# RevA.net
KiCad netlist of a schematic drawn in EAGLE
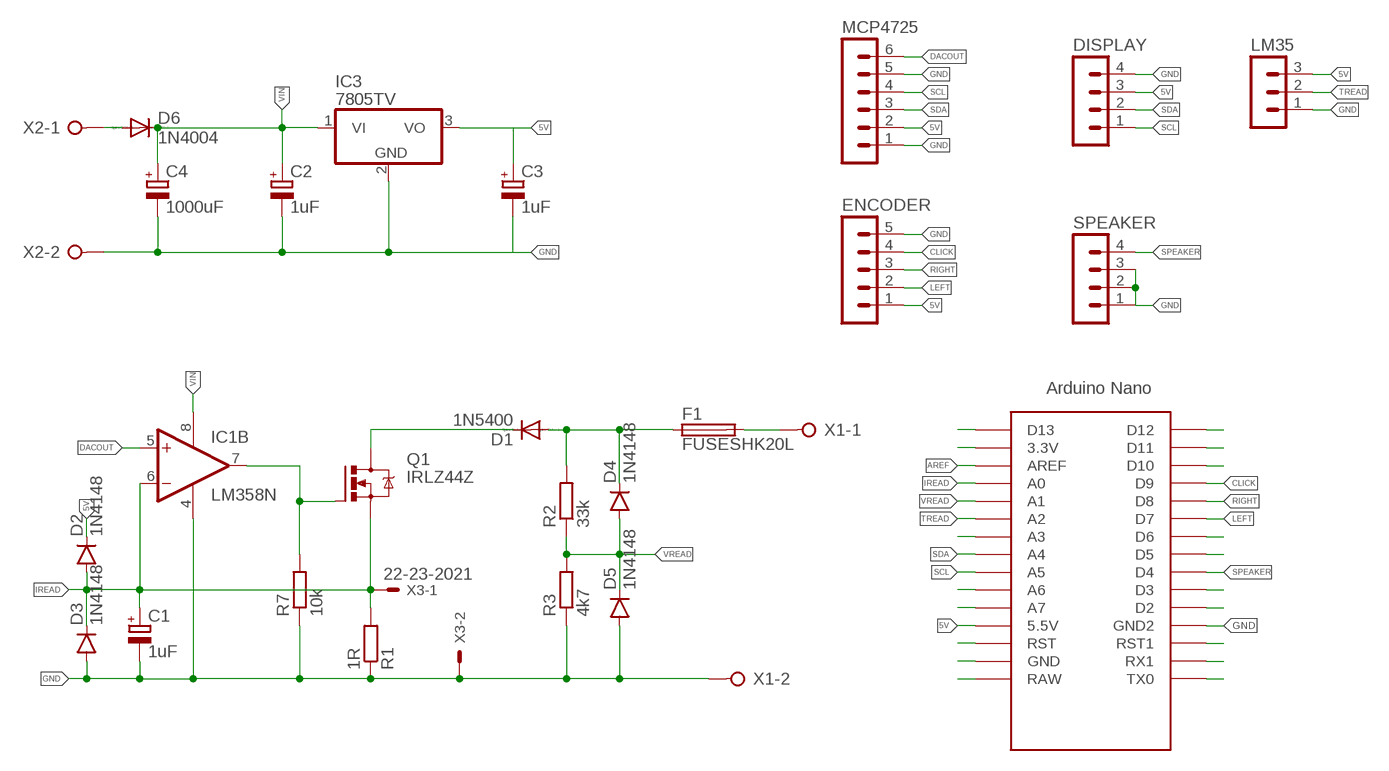
[diagram p0: schematic, sheet 1]

(export (version "E")
  (design (tool "Eeschema 10.0.6"))
  (components
    (comp (ref "C1")
      (value "1uF")
      (footprint "eagle-import:E2-5")
      (libsource (lib "eagle-import") (part "CPOL-EUE2-5"))
    )
    (comp (ref "C2")
      (value "1uF")
      (footprint "eagle-import:E5-5")
      (libsource (lib "eagle-import") (part "CPOL-EUE5-5"))
    )
    (comp (ref "C3")
      (value "1uF")
      (footprint "eagle-import:E5-5")
      (libsource (lib "eagle-import") (part "CPOL-EUE5-5"))
    )
    (comp (ref "C4")
      (value "1000uF")
      (footprint "eagle-import:E5-10,5")
      (libsource (lib "eagle-import") (part "CPOL-EUE5-10.5"))
    )
    (comp (ref "D1")
      (value "1N5400")
      (footprint "eagle-import:DO201-15")
      (libsource (lib "eagle-import") (part "1N5400"))
    )
    (comp (ref "D2")
      (value "1N4148")
      (footprint "eagle-import:DIODE-1N4148")
      (libsource (lib "eagle-import") (part "DIODE1N4148"))
    )
    (comp (ref "D3")
      (value "1N4148")
      (footprint "eagle-import:DIODE-1N4148")
      (libsource (lib "eagle-import") (part "DIODE1N4148"))
    )
    (comp (ref "D4")
      (value "1N4148")
      (footprint "eagle-import:DIODE-1N4148")
      (libsource (lib "eagle-import") (part "DIODE1N4148"))
    )
    (comp (ref "D5")
      (value "1N4148")
      (footprint "eagle-import:DIODE-1N4148")
      (libsource (lib "eagle-import") (part "DIODE1N4148"))
    )
    (comp (ref "D6")
      (value "1N4004")
      (footprint "eagle-import:DO41-10")
      (libsource (lib "eagle-import") (part "1N4004"))
    )
    (comp (ref "DISPLAY")
      (value "MA04-1")
      (footprint "eagle-import:MA04-1")
      (libsource (lib "eagle-import") (part "MA04-1"))
    )
    (comp (ref "ENCODER")
      (value "MA05-1")
      (footprint "eagle-import:MA05-1")
      (libsource (lib "eagle-import") (part "MA05-1"))
    )
    (comp (ref "F1")
      (value "FUSESHK20L")
      (footprint "eagle-import:SHK20L")
      (libsource (lib "eagle-import") (part "FUSESHK20L"))
    )
    (comp (ref "IC1")
      (value "LM358N")
      (footprint "eagle-import:DIL08")
      (libsource (lib "eagle-import") (part "LM358N"))
    )
    (comp (ref "IC3")
      (value "7805TV")
      (footprint "eagle-import:TO220V")
      (libsource (lib "eagle-import") (part "78TV05"))
    )
    (comp (ref "LM35")
      (value "MA03-1")
      (footprint "eagle-import:MA03-1")
      (libsource (lib "eagle-import") (part "MA03-1"))
    )
    (comp (ref "MCP4725")
      (value "MA06-1")
      (footprint "eagle-import:MA06-1")
      (libsource (lib "eagle-import") (part "MA06-1"))
    )
    (comp (ref "Q1")
      (value "IRLZ44Z")
      (footprint "eagle-import:TO220BH")
      (libsource (lib "eagle-import") (part "IRLZ44Z"))
    )
    (comp (ref "R1")
      (value "1R")
      (footprint "eagle-import:0309_12")
      (libsource (lib "eagle-import") (part "R-EU_0309/12"))
    )
    (comp (ref "R2")
      (value "33k")
      (footprint "eagle-import:0207_10")
      (libsource (lib "eagle-import") (part "R-EU_0207/10"))
    )
    (comp (ref "R3")
      (value "4k7")
      (footprint "eagle-import:0207_10")
      (libsource (lib "eagle-import") (part "R-EU_0207/10"))
    )
    (comp (ref "R7")
      (value "10k")
      (footprint "eagle-import:0207_10")
      (libsource (lib "eagle-import") (part "R-EU_0207/10"))
    )
    (comp (ref "SPEAKER")
      (value "MA04-1")
      (footprint "eagle-import:MA04-1")
      (libsource (lib "eagle-import") (part "MA04-1"))
    )
    (comp (ref "U$1")
      (value "NANO")
      (footprint "eagle-import:NANO")
      (libsource (lib "eagle-import") (part "NANO"))
    )
    (comp (ref "X1")
      (value "W237-02P")
      (footprint "eagle-import:W237-132")
      (libsource (lib "eagle-import") (part "W237-02P"))
    )
    (comp (ref "X2")
      (value "W237-02P")
      (footprint "eagle-import:W237-132")
      (libsource (lib "eagle-import") (part "W237-02P"))
    )
    (comp (ref "X3")
      (value "22-23-2021")
      (footprint "eagle-import:22-23-2021")
      (fields (field (name "MF") "MOLEX"))
      (libsource (lib "eagle-import") (part "22-23-2021"))
    )
  )
  (nets
    (net (code "1") (name "5V") (class "Default")
      (node (ref "C3") (pin "+") (pinfunction "+_+") (pintype "passive"))
      (node (ref "D2") (pin "C") (pinfunction "C_C") (pintype "passive"))
      (node (ref "DISPLAY") (pin "3") (pinfunction "3_3") (pintype "passive"))
      (node (ref "ENCODER") (pin "1") (pinfunction "1_1") (pintype "passive"))
      (node (ref "IC3") (pin "3") (pinfunction "VO_3") (pintype "passive"))
      (node (ref "LM35") (pin "3") (pinfunction "3_3") (pintype "passive"))
      (node (ref "MCP4725") (pin "2") (pinfunction "2_2") (pintype "passive"))
      (node (ref "U$1") (pin "5V") (pinfunction "5.5V_5V") (pintype "bidirectional"))
    )
    (net (code "2") (name "AREF") (class "Default")
      (node (ref "U$1") (pin "AREF") (pinfunction "AREF_AREF") (pintype "bidirectional"))
    )
    (net (code "3") (name "CLICK") (class "Default")
      (node (ref "ENCODER") (pin "4") (pinfunction "4_4") (pintype "passive"))
      (node (ref "U$1") (pin "D9") (pinfunction "D9_D9") (pintype "bidirectional"))
    )
    (net (code "4") (name "DACOUT") (class "Default")
      (node (ref "IC1") (pin "5") (pinfunction "+IN_5") (pintype "input"))
      (node (ref "MCP4725") (pin "6") (pinfunction "6_6") (pintype "passive"))
    )
    (net (code "5") (name "GND") (class "Default")
      (node (ref "C1") (pin "-") (pinfunction "-_-") (pintype "passive"))
      (node (ref "C2") (pin "-") (pinfunction "-_-") (pintype "passive"))
      (node (ref "C3") (pin "-") (pinfunction "-_-") (pintype "passive"))
      (node (ref "C4") (pin "-") (pinfunction "-_-") (pintype "passive"))
      (node (ref "D3") (pin "A") (pinfunction "A_A") (pintype "passive"))
      (node (ref "D5") (pin "A") (pinfunction "A_A") (pintype "passive"))
      (node (ref "DISPLAY") (pin "4") (pinfunction "4_4") (pintype "passive"))
      (node (ref "ENCODER") (pin "5") (pinfunction "5_5") (pintype "passive"))
      (node (ref "IC1") (pin "4") (pinfunction "V-_4") (pintype "power_in"))
      (node (ref "IC3") (pin "2") (pinfunction "GND_2") (pintype "passive"))
      (node (ref "LM35") (pin "1") (pinfunction "1_1") (pintype "passive"))
      (node (ref "MCP4725") (pin "1") (pinfunction "1_1") (pintype "passive"))
      (node (ref "MCP4725") (pin "5") (pinfunction "5_5") (pintype "passive"))
      (node (ref "R1") (pin "1") (pinfunction "1_1") (pintype "passive"))
      (node (ref "R3") (pin "1") (pinfunction "1_1") (pintype "passive"))
      (node (ref "R7") (pin "1") (pinfunction "1_1") (pintype "passive"))
      (node (ref "SPEAKER") (pin "1") (pinfunction "1_1") (pintype "passive"))
      (node (ref "SPEAKER") (pin "2") (pinfunction "2_2") (pintype "passive"))
      (node (ref "SPEAKER") (pin "3") (pinfunction "3_3") (pintype "passive"))
      (node (ref "U$1") (pin "GND1") (pinfunction "GND2_GND1") (pintype "bidirectional"))
      (node (ref "X1") (pin "2") (pinfunction "KL_2") (pintype "passive"))
      (node (ref "X2") (pin "2") (pinfunction "KL_2") (pintype "passive"))
      (node (ref "X3") (pin "2") (pinfunction "S_2") (pintype "passive"))
    )
    (net (code "6") (name "IREAD") (class "Default")
      (node (ref "C1") (pin "+") (pinfunction "+_+") (pintype "passive"))
      (node (ref "D2") (pin "A") (pinfunction "A_A") (pintype "passive"))
      (node (ref "D3") (pin "C") (pinfunction "C_C") (pintype "passive"))
      (node (ref "IC1") (pin "6") (pinfunction "-IN_6") (pintype "input"))
      (node (ref "Q1") (pin "S") (pinfunction "S_S") (pintype "passive"))
      (node (ref "R1") (pin "2") (pinfunction "2_2") (pintype "passive"))
      (node (ref "U$1") (pin "A0") (pinfunction "A0_A0") (pintype "bidirectional"))
      (node (ref "X3") (pin "1") (pinfunction "S_1") (pintype "passive"))
    )
    (net (code "7") (name "LEFT") (class "Default")
      (node (ref "ENCODER") (pin "2") (pinfunction "2_2") (pintype "passive"))
      (node (ref "U$1") (pin "D7") (pinfunction "D7_D7") (pintype "bidirectional"))
    )
    (net (code "8") (name "Net-(D1-PadC)") (class "Default")
      (node (ref "D1") (pin "C") (pinfunction "C_C") (pintype "passive"))
      (node (ref "Q1") (pin "D") (pinfunction "D_D") (pintype "passive"))
    )
    (net (code "9") (name "Net-(F1-1)") (class "Default")
      (node (ref "D1") (pin "A") (pinfunction "A_A") (pintype "passive"))
      (node (ref "D4") (pin "C") (pinfunction "C_C") (pintype "passive"))
      (node (ref "F1") (pin "1A") (pinfunction "1_1A") (pintype "passive"))
      (node (ref "R2") (pin "2") (pinfunction "2_2") (pintype "passive"))
    )
    (net (code "10") (name "Net-(F1-2)") (class "Default")
      (node (ref "F1") (pin "2A") (pinfunction "2_2A") (pintype "passive"))
      (node (ref "X1") (pin "1") (pinfunction "KL_1") (pintype "passive"))
    )
    (net (code "11") (name "Net-(IC1B-OUT)") (class "Default")
      (node (ref "IC1") (pin "7") (pinfunction "OUT_7") (pintype "output"))
      (node (ref "Q1") (pin "G") (pinfunction "G_G") (pintype "passive"))
      (node (ref "R7") (pin "2") (pinfunction "2_2") (pintype "passive"))
    )
    (net (code "12") (name "Net-(X2A-KL)") (class "Default")
      (node (ref "D6") (pin "A") (pinfunction "A_A") (pintype "passive"))
      (node (ref "X2") (pin "1") (pinfunction "KL_1") (pintype "passive"))
    )
    (net (code "13") (name "RIGHT") (class "Default")
      (node (ref "ENCODER") (pin "3") (pinfunction "3_3") (pintype "passive"))
      (node (ref "U$1") (pin "D8") (pinfunction "D8_D8") (pintype "bidirectional"))
    )
    (net (code "14") (name "SCL") (class "Default")
      (node (ref "DISPLAY") (pin "1") (pinfunction "1_1") (pintype "passive"))
      (node (ref "MCP4725") (pin "4") (pinfunction "4_4") (pintype "passive"))
      (node (ref "U$1") (pin "A5") (pinfunction "A5_A5") (pintype "bidirectional"))
    )
    (net (code "15") (name "SDA") (class "Default")
      (node (ref "DISPLAY") (pin "2") (pinfunction "2_2") (pintype "passive"))
      (node (ref "MCP4725") (pin "3") (pinfunction "3_3") (pintype "passive"))
      (node (ref "U$1") (pin "A4") (pinfunction "A4_A4") (pintype "bidirectional"))
    )
    (net (code "16") (name "SPEAKER") (class "Default")
      (node (ref "SPEAKER") (pin "4") (pinfunction "4_4") (pintype "passive"))
      (node (ref "U$1") (pin "D4") (pinfunction "D4_D4") (pintype "bidirectional"))
    )
    (net (code "17") (name "TREAD") (class "Default")
      (node (ref "LM35") (pin "2") (pinfunction "2_2") (pintype "passive"))
      (node (ref "U$1") (pin "A2") (pinfunction "A2_A2") (pintype "bidirectional"))
    )
    (net (code "18") (name "VIN") (class "Default")
      (node (ref "C2") (pin "+") (pinfunction "+_+") (pintype "passive"))
      (node (ref "C4") (pin "+") (pinfunction "+_+") (pintype "passive"))
      (node (ref "D6") (pin "C") (pinfunction "C_C") (pintype "passive"))
      (node (ref "IC1") (pin "8") (pinfunction "V+_8") (pintype "power_in"))
      (node (ref "IC3") (pin "1") (pinfunction "VI_1") (pintype "input"))
    )
    (net (code "19") (name "VREAD") (class "Default")
      (node (ref "D4") (pin "A") (pinfunction "A_A") (pintype "passive"))
      (node (ref "D5") (pin "C") (pinfunction "C_C") (pintype "passive"))
      (node (ref "R2") (pin "1") (pinfunction "1_1") (pintype "passive"))
      (node (ref "R3") (pin "2") (pinfunction "2_2") (pintype "passive"))
      (node (ref "U$1") (pin "A1") (pinfunction "A1_A1") (pintype "bidirectional"))
    )
    (net (code "20") (name "unconnected-(U$1-Pad3.3V)") (class "Default")
      (node (ref "U$1") (pin "3.3V") (pinfunction "3.3V_3.3V") (pintype "bidirectional"))
    )
    (net (code "21") (name "unconnected-(U$1-PadA3)") (class "Default")
      (node (ref "U$1") (pin "A3") (pinfunction "A3_A3") (pintype "bidirectional"))
    )
    (net (code "22") (name "unconnected-(U$1-PadA6)") (class "Default")
      (node (ref "U$1") (pin "A6") (pinfunction "A6_A6") (pintype "bidirectional"))
    )
    (net (code "23") (name "unconnected-(U$1-PadA7)") (class "Default")
      (node (ref "U$1") (pin "A7") (pinfunction "A7_A7") (pintype "bidirectional"))
    )
    (net (code "24") (name "unconnected-(U$1-PadD2)") (class "Default")
      (node (ref "U$1") (pin "D2") (pinfunction "D2_D2") (pintype "bidirectional"))
    )
    (net (code "25") (name "unconnected-(U$1-PadD3)") (class "Default")
      (node (ref "U$1") (pin "D3") (pinfunction "D3_D3") (pintype "bidirectional"))
    )
    (net (code "26") (name "unconnected-(U$1-PadD5)") (class "Default")
      (node (ref "U$1") (pin "D5") (pinfunction "D5_D5") (pintype "bidirectional"))
    )
    (net (code "27") (name "unconnected-(U$1-PadD6)") (class "Default")
      (node (ref "U$1") (pin "D6") (pinfunction "D6_D6") (pintype "bidirectional"))
    )
    (net (code "28") (name "unconnected-(U$1-PadD10)") (class "Default")
      (node (ref "U$1") (pin "D10") (pinfunction "D10_D10") (pintype "bidirectional"))
    )
    (net (code "29") (name "unconnected-(U$1-PadD11)") (class "Default")
      (node (ref "U$1") (pin "D11") (pinfunction "D11_D11") (pintype "bidirectional"))
    )
    (net (code "30") (name "unconnected-(U$1-PadD12)") (class "Default")
      (node (ref "U$1") (pin "D12") (pinfunction "D12_D12") (pintype "bidirectional"))
    )
    (net (code "31") (name "unconnected-(U$1-PadD13)") (class "Default")
      (node (ref "U$1") (pin "D13") (pinfunction "D13_D13") (pintype "bidirectional"))
    )
    (net (code "32") (name "unconnected-(U$1-PadGND)") (class "Default")
      (node (ref "U$1") (pin "GND") (pinfunction "GND_GND") (pintype "bidirectional"))
    )
    (net (code "33") (name "unconnected-(U$1-PadICSP1)") (class "Default")
      (node (ref "U$1") (pin "ICSP1") (pinfunction "ICSP1_ICSP1") (pintype "bidirectional"))
    )
    (net (code "34") (name "unconnected-(U$1-PadICSP2)") (class "Default")
      (node (ref "U$1") (pin "ICSP2") (pinfunction "ICSP2_ICSP2") (pintype "bidirectional"))
    )
    (net (code "35") (name "unconnected-(U$1-PadICSP3)") (class "Default")
      (node (ref "U$1") (pin "ICSP3") (pinfunction "ICSP3_ICSP3") (pintype "bidirectional"))
    )
    (net (code "36") (name "unconnected-(U$1-PadICSP4)") (class "Default")
      (node (ref "U$1") (pin "ICSP4") (pinfunction "ICSP4_ICSP4") (pintype "bidirectional"))
    )
    (net (code "37") (name "unconnected-(U$1-PadICSP5)") (class "Default")
      (node (ref "U$1") (pin "ICSP5") (pinfunction "ICSP5_ICSP5") (pintype "bidirectional"))
    )
    (net (code "38") (name "unconnected-(U$1-PadICSP6)") (class "Default")
      (node (ref "U$1") (pin "ICSP6") (pinfunction "ICSP6_ICSP6") (pintype "bidirectional"))
    )
    (net (code "39") (name "unconnected-(U$1-PadRAW)") (class "Default")
      (node (ref "U$1") (pin "RAW") (pinfunction "RAW_RAW") (pintype "bidirectional"))
    )
    (net (code "40") (name "unconnected-(U$1-PadRST)") (class "Default")
      (node (ref "U$1") (pin "RST") (pinfunction "RST_RST") (pintype "bidirectional"))
    )
    (net (code "41") (name "unconnected-(U$1-PadRST1)") (class "Default")
      (node (ref "U$1") (pin "RST1") (pinfunction "RST1_RST1") (pintype "bidirectional"))
    )
    (net (code "42") (name "unconnected-(U$1-PadRX1)") (class "Default")
      (node (ref "U$1") (pin "RX1") (pinfunction "RX1_RX1") (pintype "bidirectional"))
    )
    (net (code "43") (name "unconnected-(U$1-PadTX0)") (class "Default")
      (node (ref "U$1") (pin "TX0") (pinfunction "TX0_TX0") (pintype "bidirectional"))
    )
  )
)
